# FSWSJE2IZ6BVKJ2.net
KiCad netlist of a schematic drawn in EAGLE
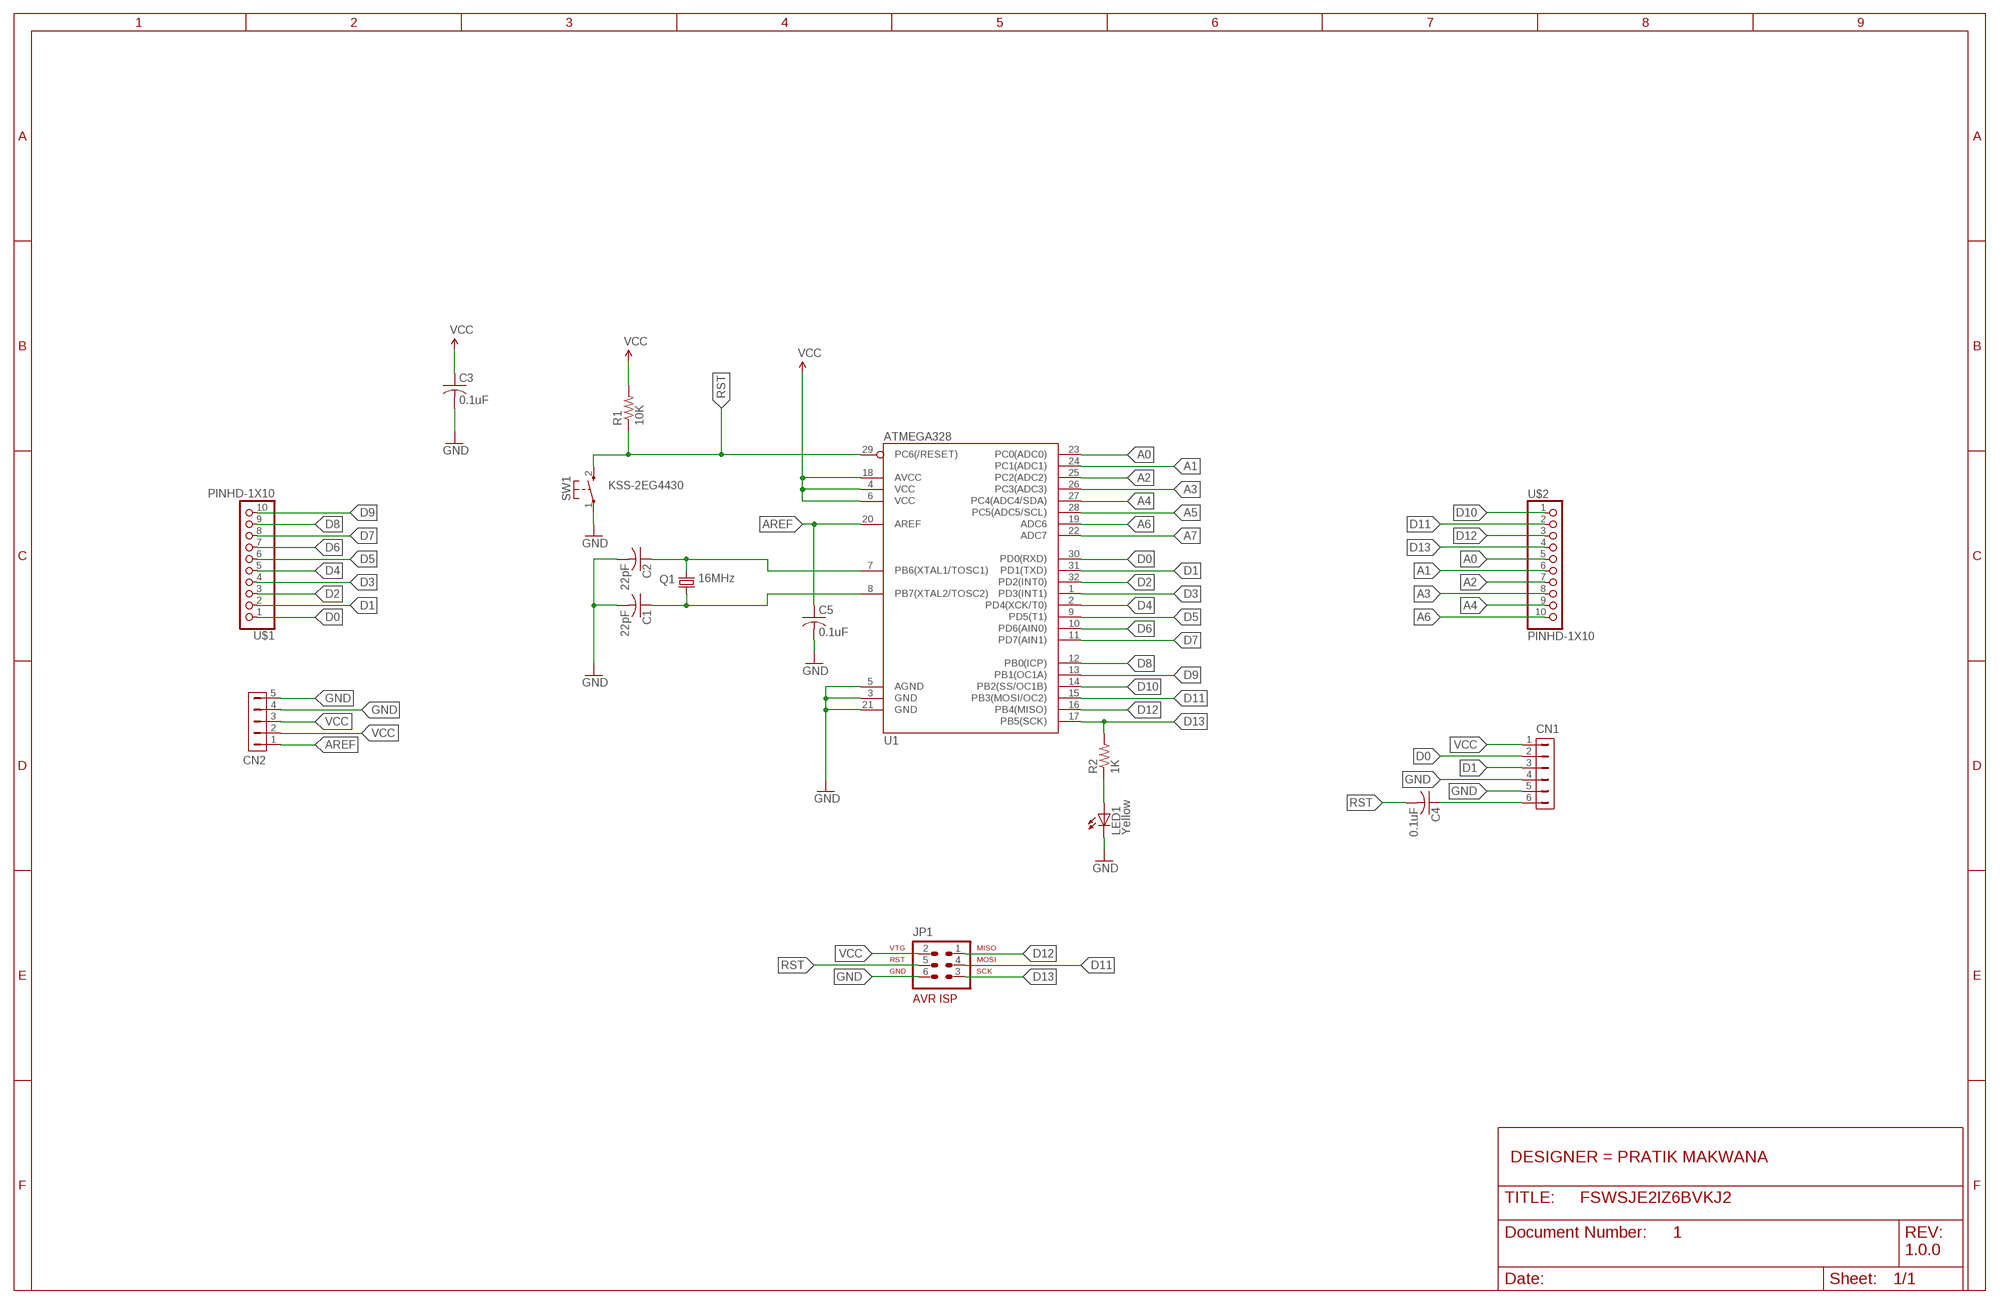
[diagram p0: schematic, sheet 1]

(export (version "E")
  (design (tool "Eeschema 10.0.6"))
  (components
    (comp (ref "C1")
      (value "22pF")
      (footprint "eagle-import:C1206")
      (libsource (lib "eagle-import") (part "C-USC1206"))
    )
    (comp (ref "C2")
      (value "22pF")
      (footprint "eagle-import:C1206")
      (libsource (lib "eagle-import") (part "C-USC1206"))
    )
    (comp (ref "C3")
      (value "0.1uF")
      (footprint "eagle-import:C0805")
      (libsource (lib "eagle-import") (part "C-USC0805"))
    )
    (comp (ref "C4")
      (value "0.1uF")
      (footprint "eagle-import:C0805")
      (libsource (lib "eagle-import") (part "C-USC0805"))
    )
    (comp (ref "C5")
      (value "0.1uF")
      (footprint "eagle-import:C0805")
      (libsource (lib "eagle-import") (part "C-USC0805"))
    )
    (comp (ref "CN1")
      (value "HDR-1X6-SIP-100")
      (footprint "eagle-import:SIP-100-6V")
      (libsource (lib "eagle-import") (part "HDR-1X6-SIP-100"))
    )
    (comp (ref "CN2")
      (value "HDR-1X5-SIP-100")
      (footprint "eagle-import:SIP-100-5V")
      (libsource (lib "eagle-import") (part "HDR-1X5-SIP-100"))
    )
    (comp (ref "JP1")
      (value "AVR-ISP-6")
      (footprint "eagle-import:AVR-ISP-6")
      (libsource (lib "eagle-import") (part "AVR-ISP-6"))
    )
    (comp (ref "LED1")
      (value "Yellow")
      (footprint "eagle-import:CHIP-LED0805")
      (libsource (lib "eagle-import") (part "LEDCHIP-LED0805"))
    )
    (comp (ref "Q1")
      (value "16MHz")
      (footprint "eagle-import:HC49_S")
      (libsource (lib "eagle-import") (part "CRYTALHC49S"))
    )
    (comp (ref "R1")
      (value "10K")
      (footprint "eagle-import:R1206")
      (libsource (lib "eagle-import") (part "R-US_R1206"))
    )
    (comp (ref "R2")
      (value "1K")
      (footprint "eagle-import:R1206")
      (libsource (lib "eagle-import") (part "R-US_R1206"))
    )
    (comp (ref "SW1")
      (value "KSS-2EG4430")
      (footprint "eagle-import:KSS-2EG4430")
      (libsource (lib "eagle-import") (part "KSS-2EG4430"))
    )
    (comp (ref "U$1")
      (value "PINHD-1X10")
      (footprint "eagle-import:1X10-BIG")
      (libsource (lib "eagle-import") (part "PINHD-1X10"))
    )
    (comp (ref "U$2")
      (value "PINHD-1X10")
      (footprint "eagle-import:1X10-BIG")
      (libsource (lib "eagle-import") (part "PINHD-1X10"))
    )
    (comp (ref "U1")
      (value "ATMEGA328")
      (footprint "eagle-import:TQFP32-08")
      (libsource (lib "eagle-import") (part "ATMEGA328"))
    )
  )
  (nets
    (net (code "1") (name "A0") (class "Default")
      (node (ref "U$2") (pin "5") (pinfunction "5_5") (pintype "passive"))
      (node (ref "U1") (pin "23") (pinfunction "PC0(ADC0)_23") (pintype "bidirectional"))
    )
    (net (code "2") (name "A1") (class "Default")
      (node (ref "U$2") (pin "6") (pinfunction "6_6") (pintype "passive"))
      (node (ref "U1") (pin "24") (pinfunction "PC1(ADC1)_24") (pintype "bidirectional"))
    )
    (net (code "3") (name "A2") (class "Default")
      (node (ref "U$2") (pin "7") (pinfunction "7_7") (pintype "passive"))
      (node (ref "U1") (pin "25") (pinfunction "PC2(ADC2)_25") (pintype "bidirectional"))
    )
    (net (code "4") (name "A3") (class "Default")
      (node (ref "U$2") (pin "8") (pinfunction "8_8") (pintype "passive"))
      (node (ref "U1") (pin "26") (pinfunction "PC3(ADC3)_26") (pintype "bidirectional"))
    )
    (net (code "5") (name "A4") (class "Default")
      (node (ref "U$2") (pin "9") (pinfunction "9_9") (pintype "passive"))
      (node (ref "U1") (pin "27") (pinfunction "PC4(ADC4/SDA)_27") (pintype "bidirectional"))
    )
    (net (code "6") (name "A5") (class "Default")
      (node (ref "U1") (pin "28") (pinfunction "PC5(ADC5/SCL)_28") (pintype "bidirectional"))
    )
    (net (code "7") (name "A6") (class "Default")
      (node (ref "U$2") (pin "10") (pinfunction "10_10") (pintype "passive"))
      (node (ref "U1") (pin "19") (pinfunction "ADC6_19") (pintype "bidirectional"))
    )
    (net (code "8") (name "A7") (class "Default")
      (node (ref "U1") (pin "22") (pinfunction "ADC7_22") (pintype "bidirectional"))
    )
    (net (code "9") (name "AREF") (class "Default")
      (node (ref "C5") (pin "1") (pinfunction "1_1") (pintype "passive"))
      (node (ref "CN2") (pin "1") (pinfunction "1_1") (pintype "passive"))
      (node (ref "U1") (pin "20") (pinfunction "AREF_20") (pintype "bidirectional"))
    )
    (net (code "10") (name "D0") (class "Default")
      (node (ref "CN1") (pin "2") (pinfunction "2_2") (pintype "passive"))
      (node (ref "U$1") (pin "1") (pinfunction "1_1") (pintype "passive"))
      (node (ref "U1") (pin "30") (pinfunction "PD0(RXD)_30") (pintype "bidirectional"))
    )
    (net (code "11") (name "D1") (class "Default")
      (node (ref "CN1") (pin "3") (pinfunction "3_3") (pintype "passive"))
      (node (ref "U$1") (pin "2") (pinfunction "2_2") (pintype "passive"))
      (node (ref "U1") (pin "31") (pinfunction "PD1(TXD)_31") (pintype "bidirectional"))
    )
    (net (code "12") (name "D2") (class "Default")
      (node (ref "U$1") (pin "3") (pinfunction "3_3") (pintype "passive"))
      (node (ref "U1") (pin "32") (pinfunction "PD2(INT0)_32") (pintype "bidirectional"))
    )
    (net (code "13") (name "D3") (class "Default")
      (node (ref "U$1") (pin "4") (pinfunction "4_4") (pintype "passive"))
      (node (ref "U1") (pin "1") (pinfunction "PD3(INT1)_1") (pintype "bidirectional"))
    )
    (net (code "14") (name "D4") (class "Default")
      (node (ref "U$1") (pin "5") (pinfunction "5_5") (pintype "passive"))
      (node (ref "U1") (pin "2") (pinfunction "PD4(XCK/T0)_2") (pintype "bidirectional"))
    )
    (net (code "15") (name "D5") (class "Default")
      (node (ref "U$1") (pin "6") (pinfunction "6_6") (pintype "passive"))
      (node (ref "U1") (pin "9") (pinfunction "PD5(T1)_9") (pintype "bidirectional"))
    )
    (net (code "16") (name "D6") (class "Default")
      (node (ref "U$1") (pin "7") (pinfunction "7_7") (pintype "passive"))
      (node (ref "U1") (pin "10") (pinfunction "PD6(AIN0)_10") (pintype "bidirectional"))
    )
    (net (code "17") (name "D7") (class "Default")
      (node (ref "U$1") (pin "8") (pinfunction "8_8") (pintype "passive"))
      (node (ref "U1") (pin "11") (pinfunction "PD7(AIN1)_11") (pintype "bidirectional"))
    )
    (net (code "18") (name "D8") (class "Default")
      (node (ref "U$1") (pin "9") (pinfunction "9_9") (pintype "passive"))
      (node (ref "U1") (pin "12") (pinfunction "PB0(ICP)_12") (pintype "bidirectional"))
    )
    (net (code "19") (name "D9") (class "Default")
      (node (ref "U$1") (pin "10") (pinfunction "10_10") (pintype "passive"))
      (node (ref "U1") (pin "13") (pinfunction "PB1(OC1A)_13") (pintype "bidirectional"))
    )
    (net (code "20") (name "D10") (class "Default")
      (node (ref "U$2") (pin "1") (pinfunction "1_1") (pintype "passive"))
      (node (ref "U1") (pin "14") (pinfunction "PB2(SS/OC1B)_14") (pintype "bidirectional"))
    )
    (net (code "21") (name "D11") (class "Default")
      (node (ref "JP1") (pin "4") (pinfunction "4_4") (pintype "passive"))
      (node (ref "U$2") (pin "2") (pinfunction "2_2") (pintype "passive"))
      (node (ref "U1") (pin "15") (pinfunction "PB3(MOSI/OC2)_15") (pintype "bidirectional"))
    )
    (net (code "22") (name "D12") (class "Default")
      (node (ref "JP1") (pin "1") (pinfunction "1_1") (pintype "passive"))
      (node (ref "U$2") (pin "3") (pinfunction "3_3") (pintype "passive"))
      (node (ref "U1") (pin "16") (pinfunction "PB4(MISO)_16") (pintype "bidirectional"))
    )
    (net (code "23") (name "D13") (class "Default")
      (node (ref "JP1") (pin "3") (pinfunction "3_3") (pintype "passive"))
      (node (ref "R2") (pin "2") (pinfunction "2_2") (pintype "passive"))
      (node (ref "U$2") (pin "4") (pinfunction "4_4") (pintype "passive"))
      (node (ref "U1") (pin "17") (pinfunction "PB5(SCK)_17") (pintype "bidirectional"))
    )
    (net (code "24") (name "GND") (class "Default")
      (node (ref "C1") (pin "2") (pinfunction "2_2") (pintype "passive"))
      (node (ref "C2") (pin "2") (pinfunction "2_2") (pintype "passive"))
      (node (ref "C3") (pin "2") (pinfunction "2_2") (pintype "passive"))
      (node (ref "C5") (pin "2") (pinfunction "2_2") (pintype "passive"))
      (node (ref "CN1") (pin "4") (pinfunction "4_4") (pintype "passive"))
      (node (ref "CN1") (pin "5") (pinfunction "5_5") (pintype "passive"))
      (node (ref "CN2") (pin "4") (pinfunction "4_4") (pintype "passive"))
      (node (ref "CN2") (pin "5") (pinfunction "5_5") (pintype "passive"))
      (node (ref "JP1") (pin "6") (pinfunction "6_6") (pintype "passive"))
      (node (ref "LED1") (pin "C") (pinfunction "C_C") (pintype "passive"))
      (node (ref "SW1") (pin "1") (pinfunction "P_1") (pintype "passive"))
      (node (ref "U1") (pin "21") (pinfunction "GND_21") (pintype "bidirectional"))
      (node (ref "U1") (pin "3") (pinfunction "GND_3") (pintype "bidirectional"))
      (node (ref "U1") (pin "5") (pinfunction "AGND_5") (pintype "bidirectional"))
    )
    (net (code "25") (name "Net-(C4-Pad1)") (class "Default")
      (node (ref "C4") (pin "1") (pinfunction "1_1") (pintype "passive"))
      (node (ref "CN1") (pin "6") (pinfunction "6_6") (pintype "passive"))
    )
    (net (code "26") (name "Net-(LED1-PadA)") (class "Default")
      (node (ref "LED1") (pin "A") (pinfunction "A_A") (pintype "passive"))
      (node (ref "R2") (pin "1") (pinfunction "1_1") (pintype "passive"))
    )
    (net (code "27") (name "Net-(U1-PB6(XTAL1{slash}TOSC1))") (class "Default")
      (node (ref "C2") (pin "1") (pinfunction "1_1") (pintype "passive"))
      (node (ref "Q1") (pin "2") (pinfunction "2_2") (pintype "passive"))
      (node (ref "U1") (pin "7") (pinfunction "PB6(XTAL1/TOSC1)_7") (pintype "bidirectional"))
    )
    (net (code "28") (name "Net-(U1-PB7(XTAL2{slash}TOSC2))") (class "Default")
      (node (ref "C1") (pin "1") (pinfunction "1_1") (pintype "passive"))
      (node (ref "Q1") (pin "1") (pinfunction "1_1") (pintype "passive"))
      (node (ref "U1") (pin "8") (pinfunction "PB7(XTAL2/TOSC2)_8") (pintype "bidirectional"))
    )
    (net (code "29") (name "RST") (class "Default")
      (node (ref "C4") (pin "2") (pinfunction "2_2") (pintype "passive"))
      (node (ref "JP1") (pin "5") (pinfunction "5_5") (pintype "passive"))
      (node (ref "R1") (pin "1") (pinfunction "1_1") (pintype "passive"))
      (node (ref "SW1") (pin "2") (pinfunction "S_2") (pintype "passive"))
      (node (ref "U1") (pin "29") (pinfunction "PC6(/RESET)_29") (pintype "bidirectional"))
    )
    (net (code "30") (name "VCC") (class "Default")
      (node (ref "C3") (pin "1") (pinfunction "1_1") (pintype "passive"))
      (node (ref "CN1") (pin "1") (pinfunction "1_1") (pintype "passive"))
      (node (ref "CN2") (pin "2") (pinfunction "2_2") (pintype "passive"))
      (node (ref "CN2") (pin "3") (pinfunction "3_3") (pintype "passive"))
      (node (ref "JP1") (pin "2") (pinfunction "2_2") (pintype "passive"))
      (node (ref "R1") (pin "2") (pinfunction "2_2") (pintype "passive"))
      (node (ref "U1") (pin "18") (pinfunction "AVCC_18") (pintype "bidirectional"))
      (node (ref "U1") (pin "4") (pinfunction "VCC_4") (pintype "bidirectional"))
      (node (ref "U1") (pin "6") (pinfunction "VCC_6") (pintype "bidirectional"))
    )
  )
)
